# CODEC.net
KiCad netlist of a schematic drawn in Altium Designer
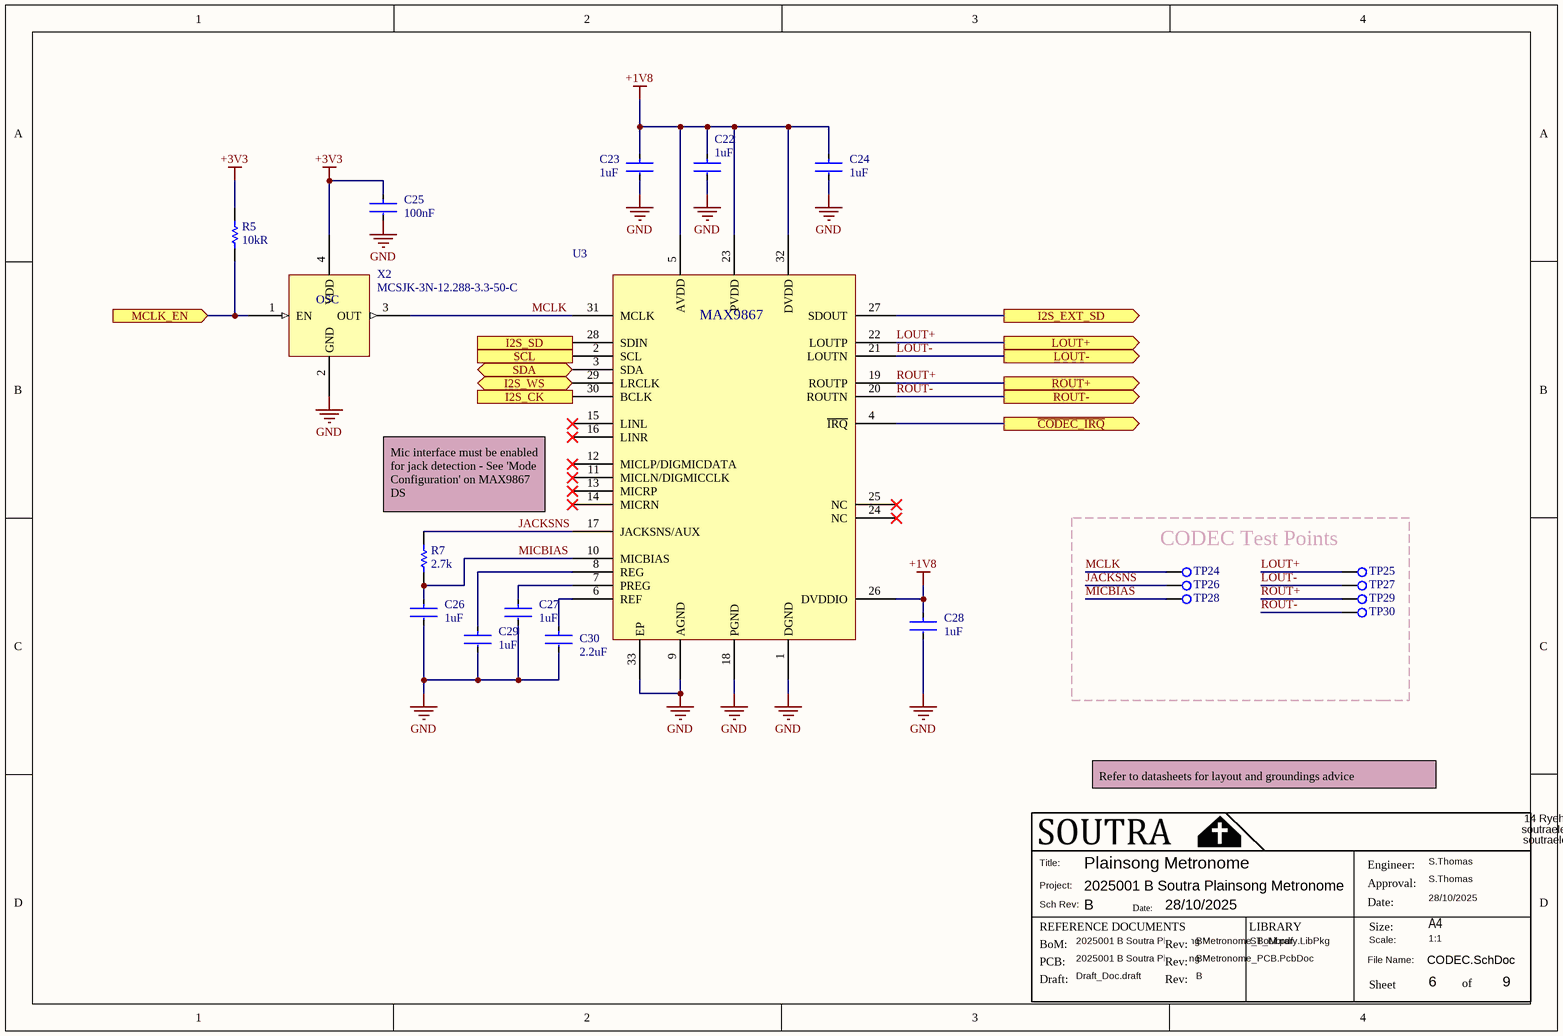
[diagram p0: CODEC.SchDoc]

(export (version "E")
  (design (tool "Eeschema 10.0.6"))
  (components
    (comp (ref "C22")
      (value "1uF")
      (footprint "CAPC1005X06L")
      (fields
        (field (name "MANUFACTURER") "Yageo")
        (field (name "MANUFACTURER PART NUMBER") "CC0402KRX5R6BB105")
        (field (name "ALTERNATIVE PART") "0402ZD105KAT2A")
      )
      (libsource (lib "ST_Library") (part "CC0402KRX5R6BB105"))
    )
    (comp (ref "C23")
      (value "1uF")
      (footprint "CAPC1005X06L")
      (fields
        (field (name "MANUFACTURER") "Yageo")
        (field (name "MANUFACTURER PART NUMBER") "CC0402KRX5R6BB105")
        (field (name "ALTERNATIVE PART") "0402ZD105KAT2A")
      )
      (libsource (lib "ST_Library") (part "CC0402KRX5R6BB105"))
    )
    (comp (ref "C24")
      (value "1uF")
      (footprint "CAPC1005X06L")
      (fields
        (field (name "MANUFACTURER") "Yageo")
        (field (name "MANUFACTURER PART NUMBER") "CC0402KRX5R6BB105")
        (field (name "ALTERNATIVE PART") "0402ZD105KAT2A")
      )
      (libsource (lib "ST_Library") (part "CC0402KRX5R6BB105"))
    )
    (comp (ref "C25")
      (value "100nF")
      (footprint "CAPC1005X06L")
      (fields
        (field (name "MANUFACTURER") "Walsin Technologies")
        (field (name "MANUFACTURER PART NUMBER") "0402X104M160CT")
        (field (name "ALTERNATIVE PART") "885012105016")
      )
      (libsource (lib "ST_Library") (part "0402X104M160CT"))
    )
    (comp (ref "C26")
      (value "1uF")
      (footprint "CAPC1005X06L")
      (fields
        (field (name "MANUFACTURER") "Yageo")
        (field (name "MANUFACTURER PART NUMBER") "CC0402KRX5R6BB105")
        (field (name "ALTERNATIVE PART") "0402ZD105KAT2A")
      )
      (libsource (lib "ST_Library") (part "CC0402KRX5R6BB105"))
    )
    (comp (ref "C27")
      (value "1uF")
      (footprint "CAPC1005X06L")
      (fields
        (field (name "MANUFACTURER") "Yageo")
        (field (name "MANUFACTURER PART NUMBER") "CC0402KRX5R6BB105")
        (field (name "ALTERNATIVE PART") "0402ZD105KAT2A")
      )
      (libsource (lib "ST_Library") (part "CC0402KRX5R6BB105"))
    )
    (comp (ref "C28")
      (value "1uF")
      (footprint "CAPC1005X06L")
      (fields
        (field (name "MANUFACTURER") "Yageo")
        (field (name "MANUFACTURER PART NUMBER") "CC0402KRX5R6BB105")
        (field (name "ALTERNATIVE PART") "0402ZD105KAT2A")
      )
      (libsource (lib "ST_Library") (part "CC0402KRX5R6BB105"))
    )
    (comp (ref "C29")
      (value "1uF")
      (footprint "CAPC1005X06L")
      (fields
        (field (name "MANUFACTURER") "Yageo")
        (field (name "MANUFACTURER PART NUMBER") "CC0402KRX5R6BB105")
        (field (name "ALTERNATIVE PART") "0402ZD105KAT2A")
      )
      (libsource (lib "ST_Library") (part "CC0402KRX5R6BB105"))
    )
    (comp (ref "C30")
      (value "2.2uF")
      (footprint "CAPC1005X06L")
      (fields
        (field (name "MANUFACTURER") "Yageo")
        (field (name "MANUFACTURER PART NUMBER") "CC0402MRX5R5BB225")
        (field (name "ALTERNATIVE PART") "MC0402X225M6R3CT")
      )
      (libsource (lib "ST_Library") (part "CC0402MRX5R5BB225"))
    )
    (comp (ref "R5")
      (value "10kR")
      (footprint "RESC_0805_2013X50X30LL20T20")
      (fields
        (field (name "MANUFACTURER") "Yageo")
        (field (name "MANUFACTURER PART NUMBER") "RC0805JR-0710KL")
        (field (name "TOLERANCE") "5%")
      )
      (libsource (lib "ST_Library") (part "RC0805JR-0710KL"))
    )
    (comp (ref "R7")
      (value "2.7k")
      (footprint "RESC_0805_2013X50X30LL20T20")
      (fields
        (field (name "MANUFACTURER") "TE Connectivity")
        (field (name "MANUFACTURER PART NUMBER") "CRGH0805F2K7")
        (field (name "ALTERNATIVE PART") "MC01W08051100R")
      )
      (libsource (lib "ST_Library") (part "CRGH0805F2K7"))
    )
    (comp (ref "TP24")
      (value "TP_CIRCLE_R1")
      (footprint "TP_CIRCLE_R1")
      (description "Test Point, SMD, Circular, Radius = 1mm")
      (libsource (lib "ST_Library") (part "TP_CIRCLE_R1"))
    )
    (comp (ref "TP25")
      (value "TP_CIRCLE_R1")
      (footprint "TP_CIRCLE_R1")
      (description "Test Point, SMD, Circular, Radius = 1mm")
      (libsource (lib "ST_Library") (part "TP_CIRCLE_R1"))
    )
    (comp (ref "TP26")
      (value "TP_CIRCLE_R1")
      (footprint "TP_CIRCLE_R1")
      (description "Test Point, SMD, Circular, Radius = 1mm")
      (libsource (lib "ST_Library") (part "TP_CIRCLE_R1"))
    )
    (comp (ref "TP27")
      (value "TP_CIRCLE_R1")
      (footprint "TP_CIRCLE_R1")
      (description "Test Point, SMD, Circular, Radius = 1mm")
      (libsource (lib "ST_Library") (part "TP_CIRCLE_R1"))
    )
    (comp (ref "TP28")
      (value "TP_CIRCLE_R1")
      (footprint "TP_CIRCLE_R1")
      (description "Test Point, SMD, Circular, Radius = 1mm")
      (libsource (lib "ST_Library") (part "TP_CIRCLE_R1"))
    )
    (comp (ref "TP29")
      (value "TP_CIRCLE_R1")
      (footprint "TP_CIRCLE_R1")
      (description "Test Point, SMD, Circular, Radius = 1mm")
      (libsource (lib "ST_Library") (part "TP_CIRCLE_R1"))
    )
    (comp (ref "TP30")
      (value "TP_CIRCLE_R1")
      (footprint "TP_CIRCLE_R1")
      (description "Test Point, SMD, Circular, Radius = 1mm")
      (libsource (lib "ST_Library") (part "TP_CIRCLE_R1"))
    )
    (comp (ref "U3")
      (value "~")
      (footprint "TQFN50P500X500X80_HS-33L")
      (description "PCM Codec")
      (fields (field (name "MANUFACTURER") "Maxim") (field (name "MANUFACTURER PART NUMBER") "MAX9867ETJ+T"))
      (libsource (lib "ST_Library") (part "MAX9867ETJ+T"))
    )
    (comp (ref "X2")
      (value "MCSJK-3N-12.288-3.3-50-C")
      (footprint "X_MULTICOMP_MCSJK-3N-12.288-3.3-50-C")
      (description "CMOS Output Clock Oscillator")
      (fields (field (name "MANUFACTURER") "Multicomp"))
      (libsource (lib "ST_Library") (part "MCSJK-3N-12.288-3.3-50-C"))
    )
  )
  (nets
    (net (code "1") (name "+1V8") (class "Default")
      (node (ref "C22") (pin "1") (pinfunction "1_1") (pintype "passive"))
      (node (ref "C23") (pin "1") (pinfunction "1_1") (pintype "passive"))
      (node (ref "C24") (pin "1") (pinfunction "1_1") (pintype "passive"))
      (node (ref "C28") (pin "1") (pinfunction "1_1") (pintype "passive"))
      (node (ref "U3") (pin "23") (pinfunction "PVDD_23") (pintype "passive"))
      (node (ref "U3") (pin "26") (pinfunction "DVDDIO_26") (pintype "passive"))
      (node (ref "U3") (pin "32") (pinfunction "DVDD_32") (pintype "passive"))
      (node (ref "U3") (pin "5") (pinfunction "AVDD_5") (pintype "passive"))
    )
    (net (code "2") (name "+3V3") (class "Default")
      (node (ref "C25") (pin "1") (pinfunction "1_1") (pintype "passive"))
      (node (ref "R5") (pin "2") (pinfunction "2_2") (pintype "passive"))
      (node (ref "X2") (pin "4") (pinfunction "VDD_4") (pintype "passive"))
    )
    (net (code "3") (name "/I2S_CK") (class "Default")
      (node (ref "U3") (pin "30") (pinfunction "BCLK_30") (pintype "passive"))
    )
    (net (code "4") (name "/I2S_EXT_SD") (class "Default")
      (node (ref "U3") (pin "27") (pinfunction "SDOUT_27") (pintype "passive"))
    )
    (net (code "5") (name "/I2S_SD") (class "Default")
      (node (ref "U3") (pin "28") (pinfunction "SDIN_28") (pintype "passive"))
    )
    (net (code "6") (name "/I2S_WS") (class "Default")
      (node (ref "U3") (pin "29") (pinfunction "LRCLK_29") (pintype "passive"))
    )
    (net (code "7") (name "/JACKSNS") (class "Default")
      (node (ref "R7") (pin "1") (pinfunction "1_1") (pintype "passive"))
      (node (ref "TP26") (pin "1") (pinfunction "1_1") (pintype "passive"))
      (node (ref "U3") (pin "17") (pinfunction "JACKSNS/AUX_17") (pintype "passive"))
    )
    (net (code "8") (name "/LOUT+") (class "Default")
      (node (ref "TP25") (pin "1") (pinfunction "1_1") (pintype "passive"))
      (node (ref "U3") (pin "22") (pinfunction "LOUTP_22") (pintype "passive"))
    )
    (net (code "9") (name "/LOUT-") (class "Default")
      (node (ref "TP27") (pin "1") (pinfunction "1_1") (pintype "passive"))
      (node (ref "U3") (pin "21") (pinfunction "LOUTN_21") (pintype "passive"))
    )
    (net (code "10") (name "/MCLK") (class "Default")
      (node (ref "TP24") (pin "1") (pinfunction "1_1") (pintype "passive"))
      (node (ref "U3") (pin "31") (pinfunction "MCLK_31") (pintype "passive"))
      (node (ref "X2") (pin "3") (pinfunction "OUT_3") (pintype "output"))
    )
    (net (code "11") (name "/MCLK_EN") (class "Default")
      (node (ref "R5") (pin "1") (pinfunction "1_1") (pintype "passive"))
      (node (ref "X2") (pin "1") (pinfunction "EN_1") (pintype "input"))
    )
    (net (code "12") (name "/MICBIAS") (class "Default")
      (node (ref "C26") (pin "1") (pinfunction "1_1") (pintype "passive"))
      (node (ref "R7") (pin "2") (pinfunction "2_2") (pintype "passive"))
      (node (ref "TP28") (pin "1") (pinfunction "1_1") (pintype "passive"))
      (node (ref "U3") (pin "10") (pinfunction "MICBIAS_10") (pintype "passive"))
    )
    (net (code "13") (name "/ROUT+") (class "Default")
      (node (ref "TP29") (pin "1") (pinfunction "1_1") (pintype "passive"))
      (node (ref "U3") (pin "19") (pinfunction "ROUTP_19") (pintype "passive"))
    )
    (net (code "14") (name "/ROUT-") (class "Default")
      (node (ref "TP30") (pin "1") (pinfunction "1_1") (pintype "passive"))
      (node (ref "U3") (pin "20") (pinfunction "ROUTN_20") (pintype "passive"))
    )
    (net (code "15") (name "/SCL") (class "Default")
      (node (ref "U3") (pin "2") (pinfunction "SCL_2") (pintype "passive"))
    )
    (net (code "16") (name "/SDA") (class "Default")
      (node (ref "U3") (pin "3") (pinfunction "SDA_3") (pintype "passive"))
    )
    (net (code "17") (name "/~{CODEC_IRQ}") (class "Default")
      (node (ref "U3") (pin "4") (pinfunction "~{IRQ}_4") (pintype "passive"))
    )
    (net (code "18") (name "GND") (class "Default")
      (node (ref "C22") (pin "2") (pinfunction "2_2") (pintype "passive"))
      (node (ref "C23") (pin "2") (pinfunction "2_2") (pintype "passive"))
      (node (ref "C24") (pin "2") (pinfunction "2_2") (pintype "passive"))
      (node (ref "C25") (pin "2") (pinfunction "2_2") (pintype "passive"))
      (node (ref "C26") (pin "2") (pinfunction "2_2") (pintype "passive"))
      (node (ref "C27") (pin "2") (pinfunction "2_2") (pintype "passive"))
      (node (ref "C28") (pin "2") (pinfunction "2_2") (pintype "passive"))
      (node (ref "C29") (pin "2") (pinfunction "2_2") (pintype "passive"))
      (node (ref "C30") (pin "2") (pinfunction "2_2") (pintype "passive"))
      (node (ref "U3") (pin "1") (pinfunction "DGND_1") (pintype "passive"))
      (node (ref "U3") (pin "18") (pinfunction "PGND_18") (pintype "passive"))
      (node (ref "U3") (pin "33") (pinfunction "EP_33") (pintype "passive"))
      (node (ref "U3") (pin "9") (pinfunction "AGND_9") (pintype "passive"))
      (node (ref "X2") (pin "2") (pinfunction "GND_2") (pintype "passive"))
    )
    (net (code "19") (name "Net-(U3-PREG)") (class "Default")
      (node (ref "C27") (pin "1") (pinfunction "1_1") (pintype "passive"))
      (node (ref "U3") (pin "7") (pinfunction "PREG_7") (pintype "passive"))
    )
    (net (code "20") (name "Net-(U3-REF)") (class "Default")
      (node (ref "C30") (pin "1") (pinfunction "1_1") (pintype "passive"))
      (node (ref "U3") (pin "6") (pinfunction "REF_6") (pintype "passive"))
    )
    (net (code "21") (name "Net-(U3-REG)") (class "Default")
      (node (ref "C29") (pin "1") (pinfunction "1_1") (pintype "passive"))
      (node (ref "U3") (pin "8") (pinfunction "REG_8") (pintype "passive"))
    )
    (net (code "22") (name "unconnected-(U3-LINL-Pad15)") (class "Default")
      (node (ref "U3") (pin "15") (pinfunction "LINL_15") (pintype "passive+no_connect"))
    )
    (net (code "23") (name "unconnected-(U3-LINR-Pad16)") (class "Default")
      (node (ref "U3") (pin "16") (pinfunction "LINR_16") (pintype "passive+no_connect"))
    )
    (net (code "24") (name "unconnected-(U3-MICLN{slash}DIGMICCLK-Pad11)") (class "Default")
      (node (ref "U3") (pin "11") (pinfunction "MICLN/DIGMICCLK_11") (pintype "passive+no_connect"))
    )
    (net (code "25") (name "unconnected-(U3-MICLP{slash}DIGMICDATA-Pad12)") (class "Default")
      (node (ref "U3") (pin "12") (pinfunction "MICLP/DIGMICDATA_12") (pintype "passive+no_connect"))
    )
    (net (code "26") (name "unconnected-(U3-MICRN-Pad14)") (class "Default")
      (node (ref "U3") (pin "14") (pinfunction "MICRN_14") (pintype "passive+no_connect"))
    )
    (net (code "27") (name "unconnected-(U3-MICRP-Pad13)") (class "Default")
      (node (ref "U3") (pin "13") (pinfunction "MICRP_13") (pintype "passive+no_connect"))
    )
    (net (code "28") (name "unconnected-(U3-NC-Pad24)") (class "Default")
      (node (ref "U3") (pin "24") (pinfunction "NC_24") (pintype "passive+no_connect"))
    )
    (net (code "29") (name "unconnected-(U3-NC-Pad25)") (class "Default")
      (node (ref "U3") (pin "25") (pinfunction "NC_25") (pintype "passive+no_connect"))
    )
  )
)
